# Power_Board_1.net
KiCad netlist of a schematic drawn in Altium Designer
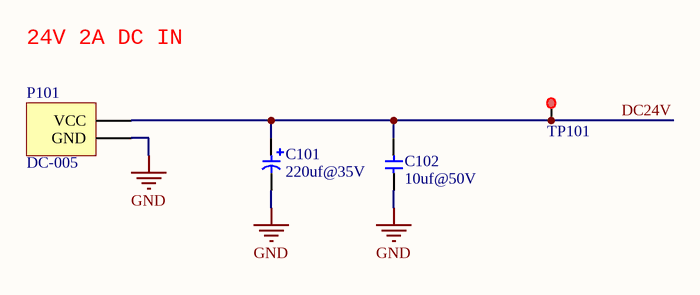
[diagram p0: Power Board.1.SchDoc]

(export (version "E")
  (design (tool "Eeschema 10.0.6"))
  (components
    (comp (ref "C101")
      (value "220uf@35V")
      (footprint "C8X12")
      (fields (field (name "Comment") "Cap2"))
      (libsource (lib "carrot_lib") (part "Cap2"))
    )
    (comp (ref "C102")
      (value "10uf@50V")
      (footprint "C1206")
      (fields (field (name "Comment") "Cap"))
      (libsource (lib "carrot_lib") (part "Cap"))
    )
    (comp (ref "P101") (value "DC-005") (footprint "DC-005") (libsource (lib "carrot_lib") (part "DC-005")))
    (comp (ref "TP101")
      (value "TestPoint")
      (footprint "TestPoint-SMD100")
      (description "测试点")
      (libsource (lib "carrot_lib") (part "TestPoint"))
    )
  )
  (nets
    (net (code "1") (name "/DC24V") (class "Default")
      (node (ref "C101") (pin "1") (pinfunction "1_1") (pintype "passive"))
      (node (ref "C102") (pin "2") (pinfunction "2_2") (pintype "passive"))
      (node (ref "P101") (pin "1") (pinfunction "VCC_1") (pintype "passive"))
      (node (ref "TP101") (pin "1") (pinfunction "1_1") (pintype "passive"))
    )
    (net (code "2") (name "GND") (class "Default")
      (node (ref "C101") (pin "2") (pinfunction "2_2") (pintype "passive"))
      (node (ref "C102") (pin "1") (pinfunction "1_1") (pintype "passive"))
      (node (ref "P101") (pin "2") (pinfunction "GND_2") (pintype "passive"))
    )
  )
)
